# PSU.net
KiCad netlist of a schematic drawn in Altium Designer
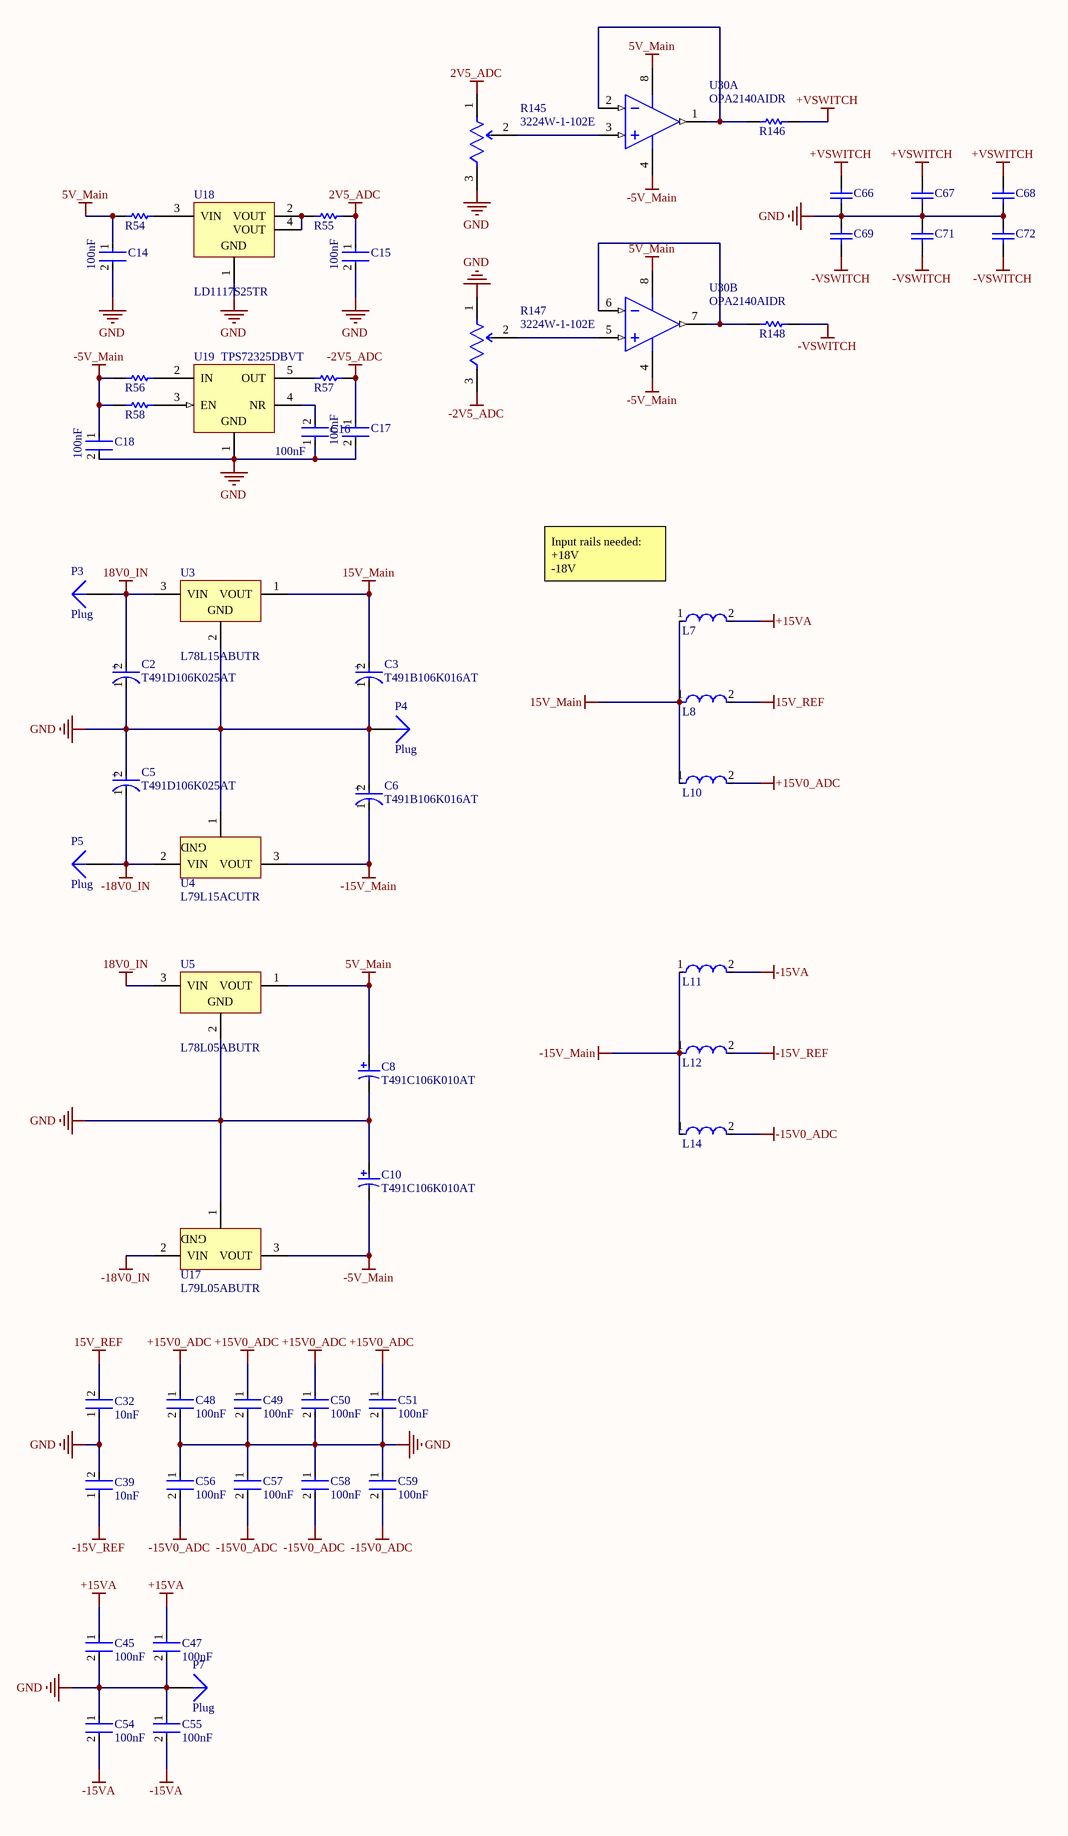
[diagram p0: PSU.SchDoc]

(export (version "E")
  (design (tool "Eeschema 10.0.6"))
  (components
    (comp (ref "C2")
      (value "T491D106K025AT")
      (footprint "FP-T491D-MFG")
      (description "CAP TANT 10UF 10% 25V 2917")
      (fields (field (name "VOLTAGE") "25V") (field (name "TOLERANCE") "20%"))
      (libsource (lib "Altium Content Vault") (part "cf48714ba7e38822c1575c7ec0b6d1f"))
    )
    (comp (ref "C3")
      (value "T491B106K016AT")
      (footprint "FP-T491B106K016AT-MFG")
      (description "CAP TANT 10UF 10% 16V 1411")
      (fields (field (name "TOLERANCE") "10%") (field (name "VOLTAGE") "16V"))
      (libsource (lib "Altium Content Vault") (part "cf48714ba7e38822c1575c7ec0b6d1f"))
    )
    (comp (ref "C5")
      (value "T491D106K025AT")
      (footprint "FP-T491D-MFG")
      (description "CAP TANT 10UF 10% 25V 2917")
      (fields (field (name "VOLTAGE") "25V") (field (name "TOLERANCE") "20%"))
      (libsource (lib "Altium Content Vault") (part "cf48714ba7e38822c1575c7ec0b6d1f"))
    )
    (comp (ref "C6")
      (value "T491B106K016AT")
      (footprint "FP-T491B106K016AT-MFG")
      (description "CAP TANT 10UF 10% 16V 1411")
      (fields (field (name "TOLERANCE") "10%") (field (name "VOLTAGE") "16V"))
      (libsource (lib "Altium Content Vault") (part "cf48714ba7e38822c1575c7ec0b6d1f"))
    )
    (comp (ref "C8")
      (value "T491C106K010AT")
      (footprint "KEMT-T491-C_L")
      (fields (field (name "MANUFACTURER") "Kemet"))
      (libsource (lib "Altium Content Vault") (part "CAP-P-2"))
    )
    (comp (ref "C10")
      (value "T491C106K010AT")
      (footprint "KEMT-T491-C_L")
      (fields (field (name "MANUFACTURER") "Kemet"))
      (libsource (lib "Altium Content Vault") (part "CAP-P-2"))
    )
    (comp (ref "C14")
      (value "100nF")
      (footprint "FP-C0805C-DN-MFG")
      (description "CAP CER 0.1UF 50V X7R 0805")
      (fields
        (field (name "MANUFACTURER PART NUMBER") "C0805C104K5RACTU")
        (field (name "MANUFACTURER") "KEMET")
      )
      (libsource (lib "Altium Content Vault") (part "b4654b650e69147ec39a6b967a45e02"))
    )
    (comp (ref "C15")
      (value "100nF")
      (footprint "FP-C0805C-DN-MFG")
      (description "CAP CER 0.1UF 50V X7R 0805")
      (fields
        (field (name "MANUFACTURER PART NUMBER") "C0805C104K5RACTU")
        (field (name "MANUFACTURER") "KEMET")
      )
      (libsource (lib "Altium Content Vault") (part "b4654b650e69147ec39a6b967a45e02"))
    )
    (comp (ref "C16")
      (value "100nF")
      (footprint "FP-C0805C-DN-MFG")
      (description "CAP CER 0.1UF 50V X7R 0805")
      (fields
        (field (name "MANUFACTURER PART NUMBER") "C0805C104K5RACTU")
        (field (name "MANUFACTURER") "KEMET")
      )
      (libsource (lib "Altium Content Vault") (part "b4654b650e69147ec39a6b967a45e02"))
    )
    (comp (ref "C17")
      (value "100nF")
      (footprint "FP-C0805C-DN-MFG")
      (description "CAP CER 0.1UF 50V X7R 0805")
      (fields
        (field (name "MANUFACTURER PART NUMBER") "C0805C104K5RACTU")
        (field (name "MANUFACTURER") "KEMET")
      )
      (libsource (lib "Altium Content Vault") (part "b4654b650e69147ec39a6b967a45e02"))
    )
    (comp (ref "C18")
      (value "100nF")
      (footprint "FP-C0805C-DN-MFG")
      (description "CAP CER 0.1UF 50V X7R 0805")
      (fields
        (field (name "MANUFACTURER PART NUMBER") "C0805C104K5RACTU")
        (field (name "MANUFACTURER") "KEMET")
      )
      (libsource (lib "Altium Content Vault") (part "b4654b650e69147ec39a6b967a45e02"))
    )
    (comp (ref "C32")
      (value "10nF")
      (footprint "FP-C0805C-DN-MFG")
      (description "CAP CER 0.1UF 50V X7R 0805")
      (fields
        (field (name "MANUFACTURER PART NUMBER") "C0805C104K5RACTU")
        (field (name "MANUFACTURER") "KEMET")
      )
      (libsource (lib "Altium Content Vault") (part "b4654b650e69147ec39a6b967a45e02"))
    )
    (comp (ref "C39")
      (value "10nF")
      (footprint "FP-C0805C-DN-MFG")
      (description "CAP CER 0.1UF 50V X7R 0805")
      (fields
        (field (name "MANUFACTURER PART NUMBER") "C0805C104K5RACTU")
        (field (name "MANUFACTURER") "KEMET")
      )
      (libsource (lib "Altium Content Vault") (part "b4654b650e69147ec39a6b967a45e02"))
    )
    (comp (ref "C45")
      (value "100nF")
      (footprint "FP-C0805C-DN-MFG")
      (description "CAP CER 0.1UF 50V X7R 0805")
      (fields
        (field (name "MANUFACTURER PART NUMBER") "C0805C104K5RACTU")
        (field (name "MANUFACTURER") "KEMET")
      )
      (libsource (lib "Altium Content Vault") (part "b4654b650e69147ec39a6b967a45e02"))
    )
    (comp (ref "C47")
      (value "100nF")
      (footprint "FP-C0805C-DN-MFG")
      (description "CAP CER 0.1UF 50V X7R 0805")
      (fields
        (field (name "MANUFACTURER PART NUMBER") "C0805C104K5RACTU")
        (field (name "MANUFACTURER") "KEMET")
      )
      (libsource (lib "Altium Content Vault") (part "b4654b650e69147ec39a6b967a45e02"))
    )
    (comp (ref "C48")
      (value "100nF")
      (footprint "FP-C0805C-DN-MFG")
      (description "CAP CER 0.1UF 50V X7R 0805")
      (fields
        (field (name "MANUFACTURER PART NUMBER") "C0805C104K5RACTU")
        (field (name "MANUFACTURER") "KEMET")
      )
      (libsource (lib "Altium Content Vault") (part "b4654b650e69147ec39a6b967a45e02"))
    )
    (comp (ref "C49")
      (value "100nF")
      (footprint "FP-C0805C-DN-MFG")
      (description "CAP CER 0.1UF 50V X7R 0805")
      (fields
        (field (name "MANUFACTURER PART NUMBER") "C0805C104K5RACTU")
        (field (name "MANUFACTURER") "KEMET")
      )
      (libsource (lib "Altium Content Vault") (part "b4654b650e69147ec39a6b967a45e02"))
    )
    (comp (ref "C50")
      (value "100nF")
      (footprint "FP-C0805C-DN-MFG")
      (description "CAP CER 0.1UF 50V X7R 0805")
      (fields
        (field (name "MANUFACTURER PART NUMBER") "C0805C104K5RACTU")
        (field (name "MANUFACTURER") "KEMET")
      )
      (libsource (lib "Altium Content Vault") (part "b4654b650e69147ec39a6b967a45e02"))
    )
    (comp (ref "C51")
      (value "100nF")
      (footprint "FP-C0805C-DN-MFG")
      (description "CAP CER 0.1UF 50V X7R 0805")
      (fields
        (field (name "MANUFACTURER PART NUMBER") "C0805C104K5RACTU")
        (field (name "MANUFACTURER") "KEMET")
      )
      (libsource (lib "Altium Content Vault") (part "b4654b650e69147ec39a6b967a45e02"))
    )
    (comp (ref "C54")
      (value "100nF")
      (footprint "FP-C0805C-DN-MFG")
      (description "CAP CER 0.1UF 50V X7R 0805")
      (fields
        (field (name "MANUFACTURER PART NUMBER") "C0805C104K5RACTU")
        (field (name "MANUFACTURER") "KEMET")
      )
      (libsource (lib "Altium Content Vault") (part "b4654b650e69147ec39a6b967a45e02"))
    )
    (comp (ref "C55")
      (value "100nF")
      (footprint "FP-C0805C-DN-MFG")
      (description "CAP CER 0.1UF 50V X7R 0805")
      (fields
        (field (name "MANUFACTURER PART NUMBER") "C0805C104K5RACTU")
        (field (name "MANUFACTURER") "KEMET")
      )
      (libsource (lib "Altium Content Vault") (part "b4654b650e69147ec39a6b967a45e02"))
    )
    (comp (ref "C56")
      (value "100nF")
      (footprint "FP-C0805C-DN-MFG")
      (description "CAP CER 0.1UF 50V X7R 0805")
      (fields
        (field (name "MANUFACTURER PART NUMBER") "C0805C104K5RACTU")
        (field (name "MANUFACTURER") "KEMET")
      )
      (libsource (lib "Altium Content Vault") (part "b4654b650e69147ec39a6b967a45e02"))
    )
    (comp (ref "C57")
      (value "100nF")
      (footprint "FP-C0805C-DN-MFG")
      (description "CAP CER 0.1UF 50V X7R 0805")
      (fields
        (field (name "MANUFACTURER PART NUMBER") "C0805C104K5RACTU")
        (field (name "MANUFACTURER") "KEMET")
      )
      (libsource (lib "Altium Content Vault") (part "b4654b650e69147ec39a6b967a45e02"))
    )
    (comp (ref "C58")
      (value "100nF")
      (footprint "FP-C0805C-DN-MFG")
      (description "CAP CER 0.1UF 50V X7R 0805")
      (fields
        (field (name "MANUFACTURER PART NUMBER") "C0805C104K5RACTU")
        (field (name "MANUFACTURER") "KEMET")
      )
      (libsource (lib "Altium Content Vault") (part "b4654b650e69147ec39a6b967a45e02"))
    )
    (comp (ref "C59")
      (value "100nF")
      (footprint "FP-C0805C-DN-MFG")
      (description "CAP CER 0.1UF 50V X7R 0805")
      (fields
        (field (name "MANUFACTURER PART NUMBER") "C0805C104K5RACTU")
        (field (name "MANUFACTURER") "KEMET")
      )
      (libsource (lib "Altium Content Vault") (part "b4654b650e69147ec39a6b967a45e02"))
    )
    (comp (ref "C66")
      (value "GRM188R71H103KA01D")
      (footprint "CAPC1608X90X35ML10T15")
      (description "Chip Capacitor, 10 nF, +/- 10%, 50 V, -55 to 125 degC, 0603 (1608 Metric), RoHS, Tape and Reel")
      (fields (field (name "VOLTAGE") "50V") (field (name "TOLERANCE") "10%"))
      (libsource (lib "Altium Content Vault") (part "CAP-NP-2"))
    )
    (comp (ref "C67")
      (value "GRM188R71H103KA01D")
      (footprint "CAPC1608X90X35ML10T15")
      (description "Chip Capacitor, 10 nF, +/- 10%, 50 V, -55 to 125 degC, 0603 (1608 Metric), RoHS, Tape and Reel")
      (fields (field (name "VOLTAGE") "50V") (field (name "TOLERANCE") "10%"))
      (libsource (lib "Altium Content Vault") (part "CAP-NP-2"))
    )
    (comp (ref "C68")
      (value "GRM188R71H103KA01D")
      (footprint "CAPC1608X90X35ML10T15")
      (description "Chip Capacitor, 10 nF, +/- 10%, 50 V, -55 to 125 degC, 0603 (1608 Metric), RoHS, Tape and Reel")
      (fields (field (name "VOLTAGE") "50V") (field (name "TOLERANCE") "10%"))
      (libsource (lib "Altium Content Vault") (part "CAP-NP-2"))
    )
    (comp (ref "C69")
      (value "GRM188R71H103KA01D")
      (footprint "CAPC1608X90X35ML10T15")
      (description "Chip Capacitor, 10 nF, +/- 10%, 50 V, -55 to 125 degC, 0603 (1608 Metric), RoHS, Tape and Reel")
      (fields (field (name "VOLTAGE") "50V") (field (name "TOLERANCE") "10%"))
      (libsource (lib "Altium Content Vault") (part "CAP-NP-2"))
    )
    (comp (ref "C71")
      (value "GRM188R71H103KA01D")
      (footprint "CAPC1608X90X35ML10T15")
      (description "Chip Capacitor, 10 nF, +/- 10%, 50 V, -55 to 125 degC, 0603 (1608 Metric), RoHS, Tape and Reel")
      (fields (field (name "VOLTAGE") "50V") (field (name "TOLERANCE") "10%"))
      (libsource (lib "Altium Content Vault") (part "CAP-NP-2"))
    )
    (comp (ref "C72")
      (value "GRM188R71H103KA01D")
      (footprint "CAPC1608X90X35ML10T15")
      (description "Chip Capacitor, 10 nF, +/- 10%, 50 V, -55 to 125 degC, 0603 (1608 Metric), RoHS, Tape and Reel")
      (fields (field (name "VOLTAGE") "50V") (field (name "TOLERANCE") "10%"))
      (libsource (lib "Altium Content Vault") (part "CAP-NP-2"))
    )
    (comp (ref "L7")
      (value "LQW15ANR10J00D")
      (footprint "FP-LQW15AN_00-W0_5-0_1-MFG")
      (description "Wire Wound RF Inductor 100nH ±5% 120mA 2.52Ω 0402 (1005)")
      (fields (field (name "TOLERANCE") "5%"))
      (libsource (lib "Altium Content Vault") (part "725321dda6339637d4d059423bc1c3c"))
    )
    (comp (ref "L8")
      (value "LQW15ANR10J00D")
      (footprint "FP-LQW15AN_00-W0_5-0_1-MFG")
      (description "Wire Wound RF Inductor 100nH ±5% 120mA 2.52Ω 0402 (1005)")
      (fields (field (name "TOLERANCE") "5%"))
      (libsource (lib "Altium Content Vault") (part "725321dda6339637d4d059423bc1c3c"))
    )
    (comp (ref "L10")
      (value "LQW15ANR10J00D")
      (footprint "FP-LQW15AN_00-W0_5-0_1-MFG")
      (description "Wire Wound RF Inductor 100nH ±5% 120mA 2.52Ω 0402 (1005)")
      (fields (field (name "TOLERANCE") "5%"))
      (libsource (lib "Altium Content Vault") (part "725321dda6339637d4d059423bc1c3c"))
    )
    (comp (ref "L11")
      (value "LQW15ANR10J00D")
      (footprint "FP-LQW15AN_00-W0_5-0_1-MFG")
      (description "Wire Wound RF Inductor 100nH ±5% 120mA 2.52Ω 0402 (1005)")
      (fields (field (name "TOLERANCE") "5%"))
      (libsource (lib "Altium Content Vault") (part "725321dda6339637d4d059423bc1c3c"))
    )
    (comp (ref "L12")
      (value "LQW15ANR10J00D")
      (footprint "FP-LQW15AN_00-W0_5-0_1-MFG")
      (description "Wire Wound RF Inductor 100nH ±5% 120mA 2.52Ω 0402 (1005)")
      (fields (field (name "TOLERANCE") "5%"))
      (libsource (lib "Altium Content Vault") (part "725321dda6339637d4d059423bc1c3c"))
    )
    (comp (ref "L14")
      (value "LQW15ANR10J00D")
      (footprint "FP-LQW15AN_00-W0_5-0_1-MFG")
      (description "Wire Wound RF Inductor 100nH ±5% 120mA 2.52Ω 0402 (1005)")
      (fields (field (name "TOLERANCE") "5%"))
      (libsource (lib "Altium Content Vault") (part "725321dda6339637d4d059423bc1c3c"))
    )
    (comp (ref "P3")
      (value "Plug")
      (footprint "PIN1")
      (fields (field (name "PUBLISHER") "Altium Limited"))
      (libsource (lib "Miscellaneous Connectors") (part "Plug"))
    )
    (comp (ref "P4")
      (value "Plug")
      (footprint "PIN1")
      (fields (field (name "PUBLISHER") "Altium Limited"))
      (libsource (lib "Miscellaneous Connectors") (part "Plug"))
    )
    (comp (ref "P5")
      (value "Plug")
      (footprint "PIN1")
      (fields (field (name "PUBLISHER") "Altium Limited"))
      (libsource (lib "Miscellaneous Connectors") (part "Plug"))
    )
    (comp (ref "P7")
      (value "Plug")
      (footprint "PIN1")
      (fields (field (name "PUBLISHER") "Altium Limited"))
      (libsource (lib "Miscellaneous Connectors") (part "Plug"))
    )
    (comp (ref "R54")
      (value "ERJ-3GEYJ202V")
      (footprint "RESC1608X55X30ML15T15")
      (fields (field (name "MANUFACTURER") "Panasonic"))
      (libsource (lib "Altium Content Vault") (part "RES"))
    )
    (comp (ref "R55")
      (value "ERJ-3GEYJ202V")
      (footprint "RESC1608X55X30ML15T15")
      (fields (field (name "MANUFACTURER") "Panasonic"))
      (libsource (lib "Altium Content Vault") (part "RES"))
    )
    (comp (ref "R56")
      (value "ERJ-3GEYJ202V")
      (footprint "RESC1608X55X30ML15T15")
      (fields (field (name "MANUFACTURER") "Panasonic"))
      (libsource (lib "Altium Content Vault") (part "RES"))
    )
    (comp (ref "R57")
      (value "ERJ-3GEYJ202V")
      (footprint "RESC1608X55X30ML15T15")
      (fields (field (name "MANUFACTURER") "Panasonic"))
      (libsource (lib "Altium Content Vault") (part "RES"))
    )
    (comp (ref "R58")
      (value "ERJ-3GEYJ202V")
      (footprint "RESC1608X55X30ML15T15")
      (fields (field (name "MANUFACTURER") "Panasonic"))
      (libsource (lib "Altium Content Vault") (part "RES"))
    )
    (comp (ref "R145")
      (value "3224W-1-102E")
      (footprint "FP-3224W-MFG")
      (description "TRIMMER 1K OHM 0.25W J LEAD TOP")
      (fields
        (field (name "TOLERANCE") "10%")
        (field (name "OCTOPART") "https://octopart.com/3224w-1-102e-bourns-23105")
      )
      (libsource (lib "Altium Content Vault") (part "13357d81287629c2fd191d242cfa50c"))
    )
    (comp (ref "R146")
      (value "ERJ-3GEYJ202V")
      (footprint "RESC1608X55X30ML15T15")
      (fields (field (name "MANUFACTURER") "Panasonic"))
      (libsource (lib "Altium Content Vault") (part "RES"))
    )
    (comp (ref "R147")
      (value "3224W-1-102E")
      (footprint "FP-3224W-MFG")
      (description "TRIMMER 1K OHM 0.25W J LEAD TOP")
      (fields
        (field (name "TOLERANCE") "10%")
        (field (name "OCTOPART") "https://octopart.com/3224w-1-102e-bourns-23105")
      )
      (libsource (lib "Altium Content Vault") (part "13357d81287629c2fd191d242cfa50c"))
    )
    (comp (ref "R148")
      (value "ERJ-3GEYJ202V")
      (footprint "RESC1608X55X30ML15T15")
      (fields (field (name "MANUFACTURER") "Panasonic"))
      (libsource (lib "Altium Content Vault") (part "RES"))
    )
    (comp (ref "U3")
      (value "L78L15ABUTR")
      (footprint "SOT-89_N")
      (description "Positive Voltage Regulator, 15V, 4-Pin SOT-89, Tape and Reel")
      (libsource (lib "Altium Content Vault") (part "PM-REG-7805-SIL3"))
    )
    (comp (ref "U4")
      (value "L79L15ACUTR")
      (footprint "SOT-89_L")
      (description "Negative Voltage Regulator, -15V, 4-Pin SOT-89, Tape and Reel")
      (libsource (lib "Altium Content Vault") (part "PM-REG-7905-SIL3A"))
    )
    (comp (ref "U5")
      (value "L78L05ABUTR")
      (footprint "SOT-89_L")
      (description "Positive Voltage Regulator, 5V, 4-Pin SOT-89, Tape and Reel")
      (libsource (lib "Altium Content Vault") (part "PM-REG-7805-SIL3"))
    )
    (comp (ref "U17")
      (value "L79L05ABUTR")
      (footprint "SOT-89_L")
      (description "Negative Voltage Regulator, -5V, 4-Pin SOT-89, Tape and Reel")
      (libsource (lib "Altium Content Vault") (part "PM-REG-7905-SIL3A"))
    )
    (comp (ref "U18")
      (value "LD1117S25TR")
      (footprint "SOT-223_L")
      (description "Fixed Low Drop Positive Voltage Regulator, 4-Pin SOT-223, Tape and Reel")
      (libsource (lib "Altium Content Vault") (part "PM-REG-LD1117-SOT4"))
    )
    (comp (ref "U19")
      (value "TPS72325DBVT")
      (footprint "DBV0005A_L")
      (fields (field (name "MANUFACTURER") "Texas Instruments"))
      (libsource (lib "Altium Content Vault") (part "TI-TPS72325-DBV5"))
    )
    (comp (ref "U30")
      (value "OPA2140AIDR")
      (footprint "D0008A_M")
      (fields (field (name "MANUFACTURER") "Texas Instruments"))
      (libsource (lib "Altium Content Vault") (part "TI-OPA-8_2"))
    )
  )
  (nets
    (net (code "1") (name "+15V0_ADC") (class "Default")
      (node (ref "C48") (pin "1") (pinfunction "1_1") (pintype "passive"))
      (node (ref "C49") (pin "1") (pinfunction "1_1") (pintype "passive"))
      (node (ref "C50") (pin "1") (pinfunction "1_1") (pintype "passive"))
      (node (ref "C51") (pin "1") (pinfunction "1_1") (pintype "passive"))
      (node (ref "L10") (pin "2") (pinfunction "2_2") (pintype "passive"))
    )
    (net (code "2") (name "+15VA") (class "Default")
      (node (ref "C45") (pin "1") (pinfunction "1_1") (pintype "passive"))
      (node (ref "C47") (pin "1") (pinfunction "1_1") (pintype "passive"))
      (node (ref "L7") (pin "2") (pinfunction "2_2") (pintype "passive"))
    )
    (net (code "3") (name "+VSWITCH") (class "Default")
      (node (ref "C66") (pin "2") (pinfunction "2_2") (pintype "passive"))
      (node (ref "C67") (pin "2") (pinfunction "2_2") (pintype "passive"))
      (node (ref "C68") (pin "2") (pinfunction "2_2") (pintype "passive"))
      (node (ref "R146") (pin "1") (pinfunction "1_1") (pintype "passive"))
    )
    (net (code "4") (name "-2V5_ADC") (class "Default")
      (node (ref "C17") (pin "1") (pinfunction "1_1") (pintype "passive"))
      (node (ref "R147") (pin "3") (pinfunction "CW_3") (pintype "passive"))
      (node (ref "R57") (pin "1") (pinfunction "1_1") (pintype "passive"))
    )
    (net (code "5") (name "-5V_Main") (class "Default")
      (node (ref "C10") (pin "2") (pinfunction "2_2") (pintype "passive"))
      (node (ref "C18") (pin "1") (pinfunction "1_1") (pintype "passive"))
      (node (ref "R56") (pin "2") (pinfunction "2_2") (pintype "passive"))
      (node (ref "R58") (pin "2") (pinfunction "2_2") (pintype "passive"))
      (node (ref "U17") (pin "3") (pinfunction "VOUT_3") (pintype "power_in"))
      (node (ref "U30") (pin "4") (pinfunction "V-_4") (pintype "power_in"))
    )
    (net (code "6") (name "-15V0_ADC") (class "Default")
      (node (ref "C56") (pin "2") (pinfunction "2_2") (pintype "passive"))
      (node (ref "C57") (pin "2") (pinfunction "2_2") (pintype "passive"))
      (node (ref "C58") (pin "2") (pinfunction "2_2") (pintype "passive"))
      (node (ref "C59") (pin "2") (pinfunction "2_2") (pintype "passive"))
      (node (ref "L14") (pin "2") (pinfunction "2_2") (pintype "passive"))
    )
    (net (code "7") (name "-15VA") (class "Default")
      (node (ref "C54") (pin "2") (pinfunction "2_2") (pintype "passive"))
      (node (ref "C55") (pin "2") (pinfunction "2_2") (pintype "passive"))
      (node (ref "L11") (pin "2") (pinfunction "2_2") (pintype "passive"))
    )
    (net (code "8") (name "-15V_Main") (class "Default")
      (node (ref "C6") (pin "1") (pinfunction "C_1") (pintype "passive"))
      (node (ref "L11") (pin "1") (pinfunction "1_1") (pintype "passive"))
      (node (ref "L12") (pin "1") (pinfunction "1_1") (pintype "passive"))
      (node (ref "L14") (pin "1") (pinfunction "1_1") (pintype "passive"))
      (node (ref "U4") (pin "3") (pinfunction "VOUT_3") (pintype "power_in"))
    )
    (net (code "9") (name "-15V_REF") (class "Default")
      (node (ref "C39") (pin "1") (pinfunction "1_1") (pintype "passive"))
      (node (ref "L12") (pin "2") (pinfunction "2_2") (pintype "passive"))
    )
    (net (code "10") (name "-18V0_IN") (class "Default")
      (node (ref "C5") (pin "1") (pinfunction "C_1") (pintype "passive"))
      (node (ref "P5") (pin "1") (pinfunction "1_1") (pintype "passive"))
      (node (ref "U17") (pin "2") (pinfunction "VIN_2") (pintype "power_in"))
      (node (ref "U4") (pin "2") (pinfunction "VIN_2") (pintype "power_in"))
    )
    (net (code "11") (name "-VSWITCH") (class "Default")
      (node (ref "C69") (pin "1") (pinfunction "1_1") (pintype "passive"))
      (node (ref "C71") (pin "1") (pinfunction "1_1") (pintype "passive"))
      (node (ref "C72") (pin "1") (pinfunction "1_1") (pintype "passive"))
      (node (ref "R148") (pin "1") (pinfunction "1_1") (pintype "passive"))
    )
    (net (code "12") (name "2V5_ADC") (class "Default")
      (node (ref "C15") (pin "1") (pinfunction "1_1") (pintype "passive"))
      (node (ref "R145") (pin "1") (pinfunction "CCW_1") (pintype "passive"))
      (node (ref "R55") (pin "1") (pinfunction "1_1") (pintype "passive"))
    )
    (net (code "13") (name "5V_Main") (class "Default")
      (node (ref "C14") (pin "1") (pinfunction "1_1") (pintype "passive"))
      (node (ref "C8") (pin "1") (pinfunction "1_1") (pintype "passive"))
      (node (ref "R54") (pin "2") (pinfunction "2_2") (pintype "passive"))
      (node (ref "U30") (pin "8") (pinfunction "V+_8") (pintype "power_in"))
      (node (ref "U5") (pin "1") (pinfunction "VOUT_1") (pintype "power_in"))
    )
    (net (code "14") (name "15V_Main") (class "Default")
      (node (ref "C3") (pin "2") (pinfunction "A_2") (pintype "passive"))
      (node (ref "L10") (pin "1") (pinfunction "1_1") (pintype "passive"))
      (node (ref "L7") (pin "1") (pinfunction "1_1") (pintype "passive"))
      (node (ref "L8") (pin "1") (pinfunction "1_1") (pintype "passive"))
      (node (ref "U3") (pin "1") (pinfunction "VOUT_1") (pintype "power_in"))
    )
    (net (code "15") (name "15V_REF") (class "Default")
      (node (ref "C32") (pin "2") (pinfunction "2_2") (pintype "passive"))
      (node (ref "L8") (pin "2") (pinfunction "2_2") (pintype "passive"))
    )
    (net (code "16") (name "18V0_IN") (class "Default")
      (node (ref "C2") (pin "2") (pinfunction "A_2") (pintype "passive"))
      (node (ref "P3") (pin "1") (pinfunction "1_1") (pintype "passive"))
      (node (ref "U3") (pin "3") (pinfunction "VIN_3") (pintype "power_in"))
      (node (ref "U5") (pin "3") (pinfunction "VIN_3") (pintype "power_in"))
    )
    (net (code "17") (name "GND") (class "Default")
      (node (ref "C10") (pin "1") (pinfunction "1_1") (pintype "passive"))
      (node (ref "C14") (pin "2") (pinfunction "2_2") (pintype "passive"))
      (node (ref "C15") (pin "2") (pinfunction "2_2") (pintype "passive"))
      (node (ref "C16") (pin "1") (pinfunction "1_1") (pintype "passive"))
      (node (ref "C17") (pin "2") (pinfunction "2_2") (pintype "passive"))
      (node (ref "C18") (pin "2") (pinfunction "2_2") (pintype "passive"))
      (node (ref "C2") (pin "1") (pinfunction "C_1") (pintype "passive"))
      (node (ref "C3") (pin "1") (pinfunction "C_1") (pintype "passive"))
      (node (ref "C32") (pin "1") (pinfunction "1_1") (pintype "passive"))
      (node (ref "C39") (pin "2") (pinfunction "2_2") (pintype "passive"))
      (node (ref "C45") (pin "2") (pinfunction "2_2") (pintype "passive"))
      (node (ref "C47") (pin "2") (pinfunction "2_2") (pintype "passive"))
      (node (ref "C48") (pin "2") (pinfunction "2_2") (pintype "passive"))
      (node (ref "C49") (pin "2") (pinfunction "2_2") (pintype "passive"))
      (node (ref "C5") (pin "2") (pinfunction "A_2") (pintype "passive"))
      (node (ref "C50") (pin "2") (pinfunction "2_2") (pintype "passive"))
      (node (ref "C51") (pin "2") (pinfunction "2_2") (pintype "passive"))
      (node (ref "C54") (pin "1") (pinfunction "1_1") (pintype "passive"))
      (node (ref "C55") (pin "1") (pinfunction "1_1") (pintype "passive"))
      (node (ref "C56") (pin "1") (pinfunction "1_1") (pintype "passive"))
      (node (ref "C57") (pin "1") (pinfunction "1_1") (pintype "passive"))
      (node (ref "C58") (pin "1") (pinfunction "1_1") (pintype "passive"))
      (node (ref "C59") (pin "1") (pinfunction "1_1") (pintype "passive"))
      (node (ref "C6") (pin "2") (pinfunction "A_2") (pintype "passive"))
      (node (ref "C66") (pin "1") (pinfunction "1_1") (pintype "passive"))
      (node (ref "C67") (pin "1") (pinfunction "1_1") (pintype "passive"))
      (node (ref "C68") (pin "1") (pinfunction "1_1") (pintype "passive"))
      (node (ref "C69") (pin "2") (pinfunction "2_2") (pintype "passive"))
      (node (ref "C71") (pin "2") (pinfunction "2_2") (pintype "passive"))
      (node (ref "C72") (pin "2") (pinfunction "2_2") (pintype "passive"))
      (node (ref "C8") (pin "2") (pinfunction "2_2") (pintype "passive"))
      (node (ref "P4") (pin "1") (pinfunction "1_1") (pintype "passive"))
      (node (ref "P7") (pin "1") (pinfunction "1_1") (pintype "passive"))
      (node (ref "R145") (pin "3") (pinfunction "CW_3") (pintype "passive"))
      (node (ref "R147") (pin "1") (pinfunction "CCW_1") (pintype "passive"))
      (node (ref "U17") (pin "1") (pinfunction "GND_1") (pintype "power_in"))
      (node (ref "U18") (pin "1") (pinfunction "GND_1") (pintype "power_in"))
      (node (ref "U19") (pin "1") (pinfunction "GND_1") (pintype "power_in"))
      (node (ref "U3") (pin "2") (pinfunction "GND_2") (pintype "power_in"))
      (node (ref "U4") (pin "1") (pinfunction "GND_1") (pintype "power_in"))
      (node (ref "U5") (pin "2") (pinfunction "GND_2") (pintype "power_in"))
    )
    (net (code "18") (name "Net-(R55-Pad2)") (class "Default")
      (node (ref "R55") (pin "2") (pinfunction "2_2") (pintype "passive"))
      (node (ref "U18") (pin "2") (pinfunction "VOUT_2") (pintype "power_in"))
      (node (ref "U18") (pin "4") (pinfunction "VOUT_4") (pintype "power_in"))
    )
    (net (code "19") (name "Net-(R145-WIPER)") (class "Default")
      (node (ref "R145") (pin "2") (pinfunction "WIPER_2") (pintype "passive"))
      (node (ref "U30") (pin "3") (pinfunction "IN_A+_3") (pintype "input"))
    )
    (net (code "20") (name "Net-(R147-WIPER)") (class "Default")
      (node (ref "R147") (pin "2") (pinfunction "WIPER_2") (pintype "passive"))
      (node (ref "U30") (pin "5") (pinfunction "IN_B+_5") (pintype "input"))
    )
    (net (code "21") (name "Net-(U18-VIN)") (class "Default")
      (node (ref "R54") (pin "1") (pinfunction "1_1") (pintype "passive"))
      (node (ref "U18") (pin "3") (pinfunction "VIN_3") (pintype "power_in"))
    )
    (net (code "22") (name "Net-(U19-EN)") (class "Default")
      (node (ref "R58") (pin "1") (pinfunction "1_1") (pintype "passive"))
      (node (ref "U19") (pin "3") (pinfunction "EN_3") (pintype "input"))
    )
    (net (code "23") (name "Net-(U19-IN)") (class "Default")
      (node (ref "R56") (pin "1") (pinfunction "1_1") (pintype "passive"))
      (node (ref "U19") (pin "2") (pinfunction "IN_2") (pintype "power_in"))
    )
    (net (code "24") (name "Net-(U19-NR)") (class "Default")
      (node (ref "C16") (pin "2") (pinfunction "2_2") (pintype "passive"))
      (node (ref "U19") (pin "4") (pinfunction "NR_4") (pintype "passive"))
    )
    (net (code "25") (name "Net-(U19-OUT)") (class "Default")
      (node (ref "R57") (pin "2") (pinfunction "2_2") (pintype "passive"))
      (node (ref "U19") (pin "5") (pinfunction "OUT_5") (pintype "power_in"))
    )
    (net (code "26") (name "Net-(U30A-IN_A-)") (class "Default")
      (node (ref "R146") (pin "2") (pinfunction "2_2") (pintype "passive"))
      (node (ref "U30") (pin "1") (pinfunction "OUT_A_1") (pintype "output"))
      (node (ref "U30") (pin "2") (pinfunction "IN_A-_2") (pintype "input"))
    )
    (net (code "27") (name "Net-(U30B-IN_B-)") (class "Default")
      (node (ref "R148") (pin "2") (pinfunction "2_2") (pintype "passive"))
      (node (ref "U30") (pin "6") (pinfunction "IN_B-_6") (pintype "input"))
      (node (ref "U30") (pin "7") (pinfunction "OUT_B_7") (pintype "output"))
    )
  )
)
